# Power.net
KiCad netlist of a schematic drawn in Altium Designer
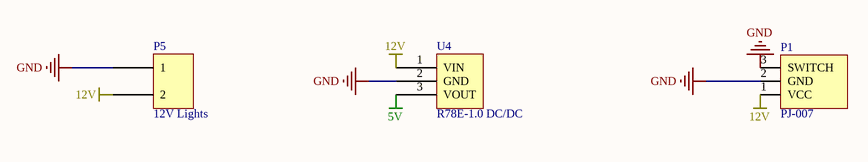
[diagram p0: Power.SchDoc]

(export (version "E")
  (design (tool "Eeschema 10.0.6"))
  (components
    (comp (ref "P1")
      (value "PJ-007")
      (footprint "BARREL JACK PJ007")
      (libsource (lib "BARREL JACK PJ-007") (part "Component_1"))
    )
    (comp (ref "P5")
      (value "12V Lights")
      (footprint "Molex Mini-Fit Jr 2x1")
      (libsource (lib "Molex Mini-Fit Jr 1x2") (part "Molex Mini-Fit 1x2"))
    )
    (comp (ref "U4")
      (value "R78E-1.0 DC/DC")
      (footprint "R78-1.0")
      (libsource (lib "R78E-1.0_DCDC_SCH") (part "R78E-1.0"))
    )
  )
  (nets
    (net (code "1") (name "5V") (class "Default")
      (node (ref "U4") (pin "3") (pinfunction "VOUT_3") (pintype "passive"))
    )
    (net (code "2") (name "12V") (class "Default")
      (node (ref "P1") (pin "1") (pinfunction "VCC_1") (pintype "passive"))
      (node (ref "P5") (pin "2") (pinfunction "2_2") (pintype "passive"))
      (node (ref "U4") (pin "1") (pinfunction "VIN_1") (pintype "passive"))
    )
    (net (code "3") (name "GND") (class "Default")
      (node (ref "P1") (pin "2") (pinfunction "GND_2") (pintype "passive"))
      (node (ref "P1") (pin "3") (pinfunction "SWITCH_3") (pintype "passive"))
      (node (ref "P5") (pin "1") (pinfunction "1_1") (pintype "passive"))
      (node (ref "U4") (pin "2") (pinfunction "GND_2") (pintype "passive"))
    )
  )
)
